# reflow.net
KiCad netlist of a schematic drawn in EAGLE
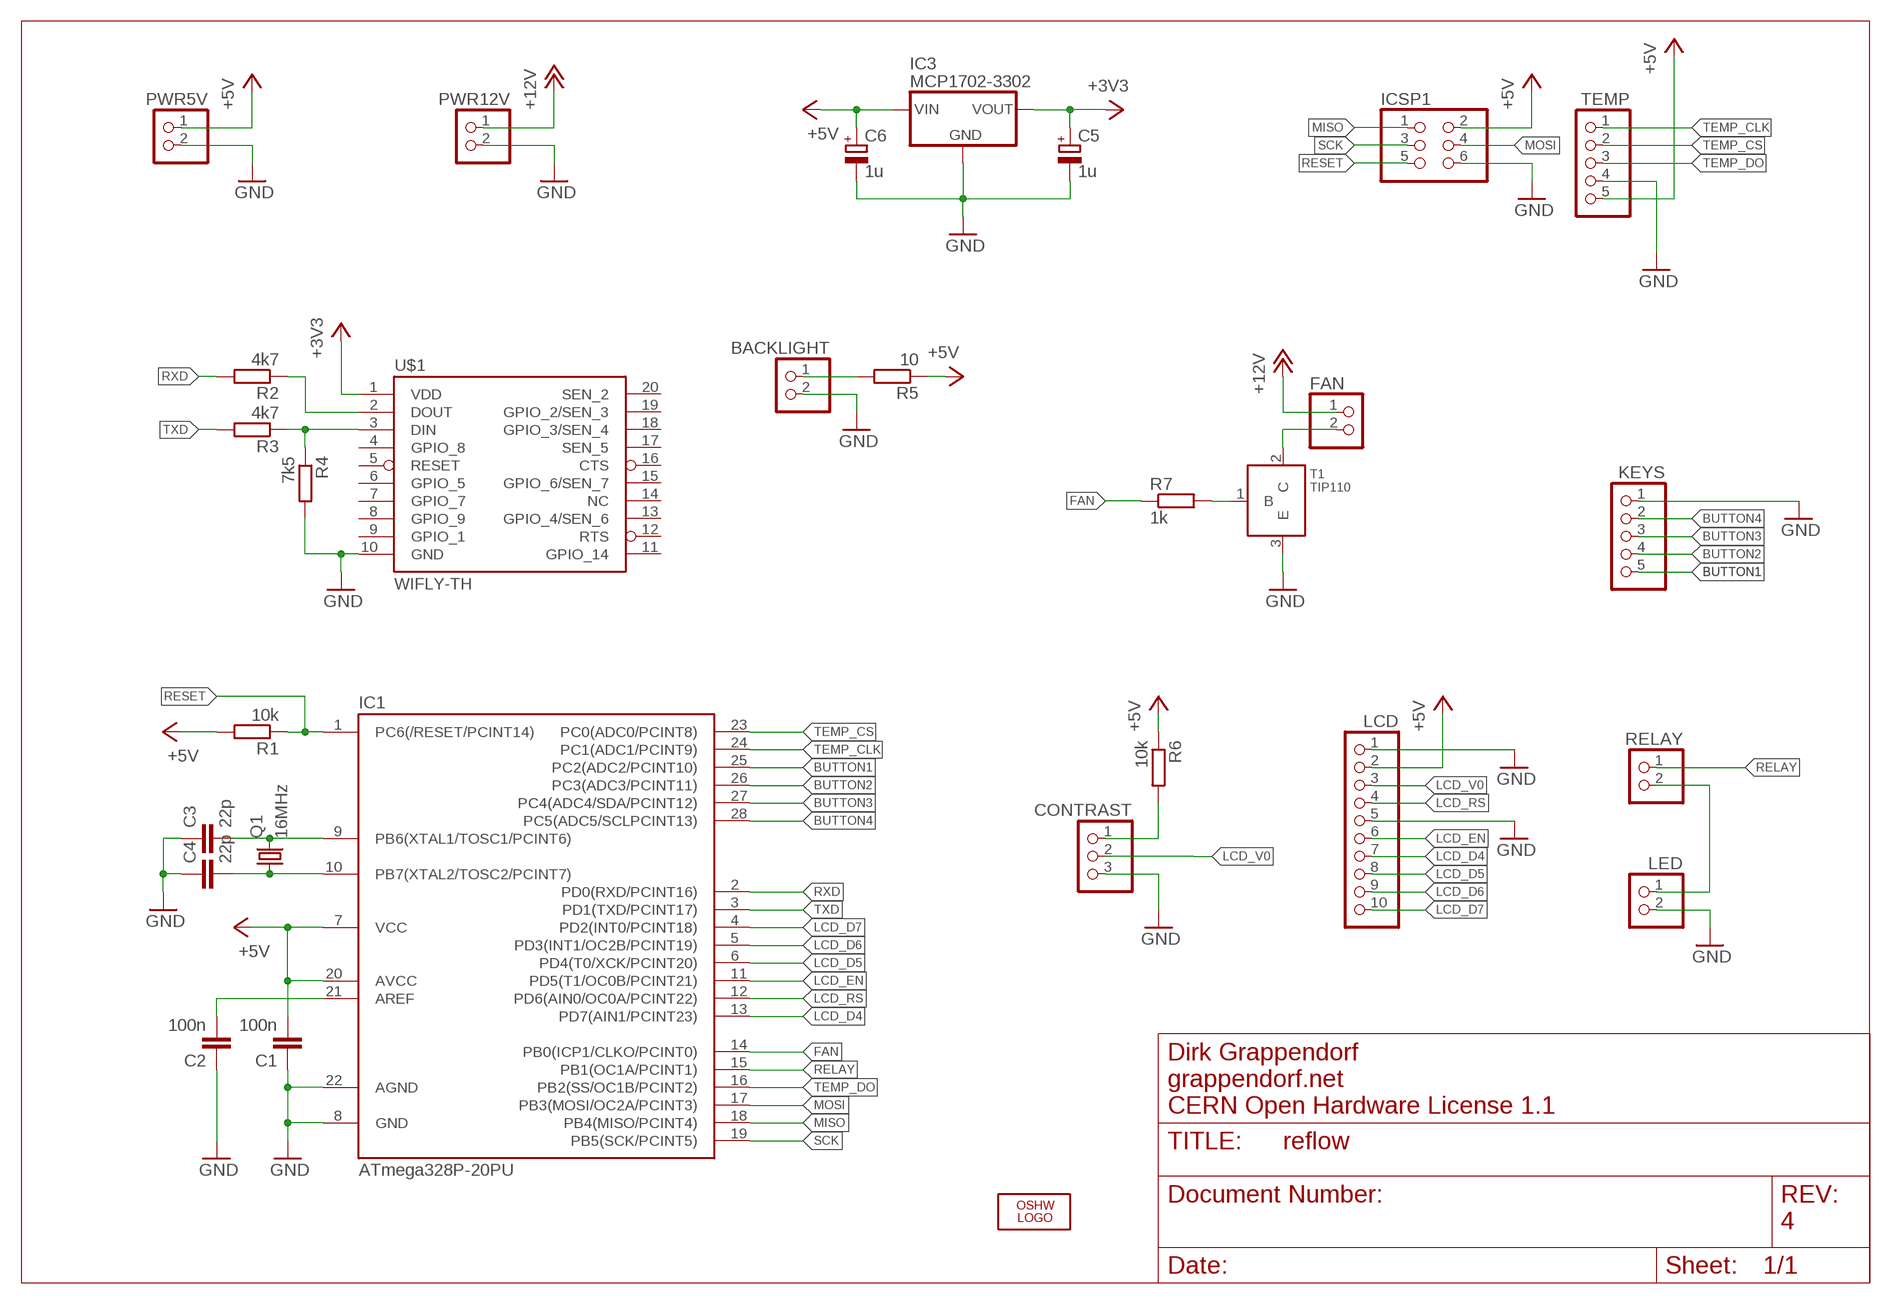
[diagram p0: schematic, sheet 1]

(export (version "E")
  (design (tool "Eeschema 10.0.6"))
  (components
    (comp (ref "BACKLIGHT")
      (value "PINHD-1X2")
      (footprint "eagle-import:1X02")
      (libsource (lib "eagle-import") (part "PINHD-1X2"))
    )
    (comp (ref "C1")
      (value "100n")
      (footprint "eagle-import:C025-024X044")
      (libsource (lib "eagle-import") (part "C-EU025-024X044"))
    )
    (comp (ref "C2")
      (value "100n")
      (footprint "eagle-import:C025-024X044")
      (libsource (lib "eagle-import") (part "C-EU025-024X044"))
    )
    (comp (ref "C3")
      (value "22p")
      (footprint "eagle-import:C025-025X050")
      (libsource (lib "eagle-import") (part "C-EU025-025X050"))
    )
    (comp (ref "C4")
      (value "22p")
      (footprint "eagle-import:C025-025X050")
      (libsource (lib "eagle-import") (part "C-EU025-025X050"))
    )
    (comp (ref "C5")
      (value "1u")
      (footprint "eagle-import:E2,5-5")
      (libsource (lib "eagle-import") (part "CPOL-EUE2.5-5"))
    )
    (comp (ref "C6")
      (value "1u")
      (footprint "eagle-import:E2,5-5")
      (libsource (lib "eagle-import") (part "CPOL-EUE2.5-5"))
    )
    (comp (ref "CONTRAST")
      (value "PINHD-1X3")
      (footprint "eagle-import:1X03")
      (libsource (lib "eagle-import") (part "PINHD-1X3"))
    )
    (comp (ref "FAN")
      (value "PINHD-1X2")
      (footprint "eagle-import:1X02")
      (libsource (lib "eagle-import") (part "PINHD-1X2"))
    )
    (comp (ref "IC1")
      (value "ATmega328P-20PU")
      (footprint "eagle-import:DIL28-3")
      (libsource (lib "eagle-import") (part "ATMEGA48/88/168-PU"))
    )
    (comp (ref "IC3")
      (value "MCP1702-3302")
      (footprint "eagle-import:MCP1702")
      (libsource (lib "eagle-import") (part "MCP1702"))
    )
    (comp (ref "ICSP1")
      (value "PINHD-2X03_2.54")
      (footprint "eagle-import:2X03")
      (libsource (lib "eagle-import") (part "PINHD-2X03_2.54"))
    )
    (comp (ref "KEYS")
      (value "PINHD-1X5")
      (footprint "eagle-import:1X05")
      (libsource (lib "eagle-import") (part "PINHD-1X5"))
    )
    (comp (ref "LCD")
      (value "PINHD-1X10")
      (footprint "eagle-import:1X10")
      (libsource (lib "eagle-import") (part "PINHD-1X10"))
    )
    (comp (ref "LED")
      (value "PINHD-1X2")
      (footprint "eagle-import:1X02")
      (libsource (lib "eagle-import") (part "PINHD-1X2"))
    )
    (comp (ref "LOGO1")
      (value "OSHW_LOGO_10MILX0350-NT-BOTTOM")
      (footprint "eagle-import:OSHW_10X350_NOTEXT_BOTTOM")
      (libsource (lib "eagle-import") (part "OSHW_LOGO_10MILX0350-NT-BOTTOM"))
    )
    (comp (ref "PWR5V")
      (value "PINHD-1X2")
      (footprint "eagle-import:1X02")
      (libsource (lib "eagle-import") (part "PINHD-1X2"))
    )
    (comp (ref "PWR12V")
      (value "PINHD-1X2")
      (footprint "eagle-import:1X02")
      (libsource (lib "eagle-import") (part "PINHD-1X2"))
    )
    (comp (ref "Q1")
      (value "16MHz")
      (footprint "eagle-import:HC49U-V")
      (libsource (lib "eagle-import") (part "CRYSTALHC49U-V"))
    )
    (comp (ref "R1")
      (value "10k")
      (footprint "eagle-import:0204_7")
      (libsource (lib "eagle-import") (part "R-EU_0204/7"))
    )
    (comp (ref "R2")
      (value "4k7")
      (footprint "eagle-import:0204_7")
      (libsource (lib "eagle-import") (part "R-EU_0204/7"))
    )
    (comp (ref "R3")
      (value "4k7")
      (footprint "eagle-import:0204_7")
      (libsource (lib "eagle-import") (part "R-EU_0204/7"))
    )
    (comp (ref "R4")
      (value "7k5")
      (footprint "eagle-import:0204_7")
      (libsource (lib "eagle-import") (part "R-EU_0204/7"))
    )
    (comp (ref "R5")
      (value "10")
      (footprint "eagle-import:0204_7")
      (libsource (lib "eagle-import") (part "R-EU_0204/7"))
    )
    (comp (ref "R6")
      (value "10k")
      (footprint "eagle-import:0204_7")
      (libsource (lib "eagle-import") (part "R-EU_0204/7"))
    )
    (comp (ref "R7")
      (value "1k")
      (footprint "eagle-import:0204_7")
      (libsource (lib "eagle-import") (part "R-EU_0204/7"))
    )
    (comp (ref "RELAY")
      (value "PINHD-1X2")
      (footprint "eagle-import:1X02")
      (libsource (lib "eagle-import") (part "PINHD-1X2"))
    )
    (comp (ref "T1")
      (value "TIP110")
      (footprint "eagle-import:T0220")
      (libsource (lib "eagle-import") (part "TIP112"))
    )
    (comp (ref "TEMP")
      (value "PINHD-1X5")
      (footprint "eagle-import:1X05")
      (libsource (lib "eagle-import") (part "PINHD-1X5"))
    )
    (comp (ref "U$1")
      (value "WIFLY-TH")
      (footprint "eagle-import:WIFLY-TH")
      (libsource (lib "eagle-import") (part "WIFLY-TH"))
    )
  )
  (nets
    (net (code "1") (name "+3V3") (class "Default")
      (node (ref "C5") (pin "+") (pinfunction "+_+") (pintype "passive"))
      (node (ref "IC3") (pin "VOUT") (pinfunction "OUT_VOUT") (pintype "passive"))
      (node (ref "U$1") (pin "1") (pinfunction "VDD_1") (pintype "power_in"))
    )
    (net (code "2") (name "+5V") (class "Default")
      (node (ref "C1") (pin "2") (pinfunction "2_2") (pintype "passive"))
      (node (ref "C6") (pin "+") (pinfunction "+_+") (pintype "passive"))
      (node (ref "IC1") (pin "20") (pinfunction "AVCC_20") (pintype "passive"))
      (node (ref "IC1") (pin "7") (pinfunction "VCC_7") (pintype "power_in"))
      (node (ref "IC3") (pin "VIN") (pinfunction "IN_VIN") (pintype "input"))
      (node (ref "ICSP1") (pin "2") (pinfunction "2_2") (pintype "passive"))
      (node (ref "LCD") (pin "2") (pinfunction "2_2") (pintype "passive"))
      (node (ref "PWR5V") (pin "1") (pinfunction "1_1") (pintype "passive"))
      (node (ref "R1") (pin "2") (pinfunction "2_2") (pintype "passive"))
      (node (ref "R5") (pin "1") (pinfunction "1_1") (pintype "passive"))
      (node (ref "R6") (pin "1") (pinfunction "1_1") (pintype "passive"))
      (node (ref "TEMP") (pin "5") (pinfunction "5_5") (pintype "passive"))
    )
    (net (code "3") (name "+12V") (class "Default")
      (node (ref "FAN") (pin "1") (pinfunction "1_1") (pintype "passive"))
      (node (ref "PWR12V") (pin "1") (pinfunction "1_1") (pintype "passive"))
    )
    (net (code "4") (name "BUTTON1") (class "Default")
      (node (ref "IC1") (pin "25") (pinfunction "PC2(ADC2/PCINT10)_25") (pintype "bidirectional"))
      (node (ref "KEYS") (pin "5") (pinfunction "5_5") (pintype "passive"))
    )
    (net (code "5") (name "BUTTON2") (class "Default")
      (node (ref "IC1") (pin "26") (pinfunction "PC3(ADC3/PCINT11)_26") (pintype "bidirectional"))
      (node (ref "KEYS") (pin "4") (pinfunction "4_4") (pintype "passive"))
    )
    (net (code "6") (name "BUTTON3") (class "Default")
      (node (ref "IC1") (pin "27") (pinfunction "PC4(ADC4/SDA/PCINT12)_27") (pintype "bidirectional"))
      (node (ref "KEYS") (pin "3") (pinfunction "3_3") (pintype "passive"))
    )
    (net (code "7") (name "BUTTON4") (class "Default")
      (node (ref "IC1") (pin "28") (pinfunction "PC5(ADC5/SCLPCINT13)_28") (pintype "bidirectional"))
      (node (ref "KEYS") (pin "2") (pinfunction "2_2") (pintype "passive"))
    )
    (net (code "8") (name "FAN") (class "Default")
      (node (ref "IC1") (pin "14") (pinfunction "PB0(ICP1/CLKO/PCINT0)_14") (pintype "bidirectional"))
      (node (ref "R7") (pin "1") (pinfunction "1_1") (pintype "passive"))
    )
    (net (code "9") (name "GND") (class "Default")
      (node (ref "BACKLIGHT") (pin "2") (pinfunction "2_2") (pintype "passive"))
      (node (ref "C1") (pin "1") (pinfunction "1_1") (pintype "passive"))
      (node (ref "C2") (pin "1") (pinfunction "1_1") (pintype "passive"))
      (node (ref "C3") (pin "1") (pinfunction "1_1") (pintype "passive"))
      (node (ref "C4") (pin "1") (pinfunction "1_1") (pintype "passive"))
      (node (ref "C5") (pin "-") (pinfunction "-_-") (pintype "passive"))
      (node (ref "C6") (pin "-") (pinfunction "-_-") (pintype "passive"))
      (node (ref "CONTRAST") (pin "3") (pinfunction "3_3") (pintype "passive"))
      (node (ref "IC1") (pin "22") (pinfunction "AGND_22") (pintype "power_in"))
      (node (ref "IC1") (pin "8") (pinfunction "GND_8") (pintype "power_in"))
      (node (ref "IC3") (pin "GND") (pinfunction "GND_GND") (pintype "input"))
      (node (ref "ICSP1") (pin "6") (pinfunction "6_6") (pintype "passive"))
      (node (ref "KEYS") (pin "1") (pinfunction "1_1") (pintype "passive"))
      (node (ref "LCD") (pin "1") (pinfunction "1_1") (pintype "passive"))
      (node (ref "LCD") (pin "5") (pinfunction "5_5") (pintype "passive"))
      (node (ref "LED") (pin "2") (pinfunction "2_2") (pintype "passive"))
      (node (ref "PWR12V") (pin "2") (pinfunction "2_2") (pintype "passive"))
      (node (ref "PWR5V") (pin "2") (pinfunction "2_2") (pintype "passive"))
      (node (ref "R4") (pin "2") (pinfunction "2_2") (pintype "passive"))
      (node (ref "T1") (pin "3") (pinfunction "E_3") (pintype "bidirectional"))
      (node (ref "TEMP") (pin "4") (pinfunction "4_4") (pintype "passive"))
      (node (ref "U$1") (pin "10") (pinfunction "GND_10") (pintype "power_in"))
    )
    (net (code "10") (name "LCD_D4") (class "Default")
      (node (ref "IC1") (pin "13") (pinfunction "PD7(AIN1/PCINT23)_13") (pintype "bidirectional"))
      (node (ref "LCD") (pin "7") (pinfunction "7_7") (pintype "passive"))
    )
    (net (code "11") (name "LCD_D5") (class "Default")
      (node (ref "IC1") (pin "6") (pinfunction "PD4(T0/XCK/PCINT20)_6") (pintype "bidirectional"))
      (node (ref "LCD") (pin "8") (pinfunction "8_8") (pintype "passive"))
    )
    (net (code "12") (name "LCD_D6") (class "Default")
      (node (ref "IC1") (pin "5") (pinfunction "PD3(INT1/OC2B/PCINT19)_5") (pintype "bidirectional"))
      (node (ref "LCD") (pin "9") (pinfunction "9_9") (pintype "passive"))
    )
    (net (code "13") (name "LCD_D7") (class "Default")
      (node (ref "IC1") (pin "4") (pinfunction "PD2(INT0/PCINT18)_4") (pintype "bidirectional"))
      (node (ref "LCD") (pin "10") (pinfunction "10_10") (pintype "passive"))
    )
    (net (code "14") (name "LCD_EN") (class "Default")
      (node (ref "IC1") (pin "11") (pinfunction "PD5(T1/OC0B/PCINT21)_11") (pintype "bidirectional"))
      (node (ref "LCD") (pin "6") (pinfunction "6_6") (pintype "passive"))
    )
    (net (code "15") (name "LCD_RS") (class "Default")
      (node (ref "IC1") (pin "12") (pinfunction "PD6(AIN0/OC0A/PCINT22)_12") (pintype "bidirectional"))
      (node (ref "LCD") (pin "4") (pinfunction "4_4") (pintype "passive"))
    )
    (net (code "16") (name "LCD_V0") (class "Default")
      (node (ref "CONTRAST") (pin "2") (pinfunction "2_2") (pintype "passive"))
      (node (ref "LCD") (pin "3") (pinfunction "3_3") (pintype "passive"))
    )
    (net (code "17") (name "MISO") (class "Default")
      (node (ref "IC1") (pin "18") (pinfunction "PB4(MISO/PCINT4)_18") (pintype "bidirectional"))
      (node (ref "ICSP1") (pin "1") (pinfunction "1_1") (pintype "passive"))
    )
    (net (code "18") (name "MOSI") (class "Default")
      (node (ref "IC1") (pin "17") (pinfunction "PB3(MOSI/OC2A/PCINT3)_17") (pintype "bidirectional"))
      (node (ref "ICSP1") (pin "4") (pinfunction "4_4") (pintype "passive"))
    )
    (net (code "19") (name "Net-(BACKLIGHT-Pad1)") (class "Default")
      (node (ref "BACKLIGHT") (pin "1") (pinfunction "1_1") (pintype "passive"))
      (node (ref "R5") (pin "2") (pinfunction "2_2") (pintype "passive"))
    )
    (net (code "20") (name "Net-(CONTRAST-Pad1)") (class "Default")
      (node (ref "CONTRAST") (pin "1") (pinfunction "1_1") (pintype "passive"))
      (node (ref "R6") (pin "2") (pinfunction "2_2") (pintype "passive"))
    )
    (net (code "21") (name "Net-(IC1-AREF)") (class "Default")
      (node (ref "C2") (pin "2") (pinfunction "2_2") (pintype "passive"))
      (node (ref "IC1") (pin "21") (pinfunction "AREF_21") (pintype "passive"))
    )
    (net (code "22") (name "Net-(IC1-PB6(XTAL1{slash}TOSC1{slash}PCINT6))") (class "Default")
      (node (ref "C3") (pin "2") (pinfunction "2_2") (pintype "passive"))
      (node (ref "IC1") (pin "9") (pinfunction "PB6(XTAL1/TOSC1/PCINT6)_9") (pintype "bidirectional"))
      (node (ref "Q1") (pin "2") (pinfunction "2_2") (pintype "passive"))
    )
    (net (code "23") (name "Net-(IC1-PB7(XTAL2{slash}TOSC2{slash}PCINT7))") (class "Default")
      (node (ref "C4") (pin "2") (pinfunction "2_2") (pintype "passive"))
      (node (ref "IC1") (pin "10") (pinfunction "PB7(XTAL2/TOSC2/PCINT7)_10") (pintype "bidirectional"))
      (node (ref "Q1") (pin "1") (pinfunction "1_1") (pintype "passive"))
    )
    (net (code "24") (name "Net-(LED-Pad1)") (class "Default")
      (node (ref "LED") (pin "1") (pinfunction "1_1") (pintype "passive"))
      (node (ref "RELAY") (pin "2") (pinfunction "2_2") (pintype "passive"))
    )
    (net (code "25") (name "Net-(T1-B)") (class "Default")
      (node (ref "R7") (pin "2") (pinfunction "2_2") (pintype "passive"))
      (node (ref "T1") (pin "1") (pinfunction "B_1") (pintype "bidirectional"))
    )
    (net (code "26") (name "Net-(T1-C)") (class "Default")
      (node (ref "FAN") (pin "2") (pinfunction "2_2") (pintype "passive"))
      (node (ref "T1") (pin "2") (pinfunction "C_2") (pintype "bidirectional"))
    )
    (net (code "27") (name "Net-(U$1-DIN)") (class "Default")
      (node (ref "R3") (pin "1") (pinfunction "1_1") (pintype "passive"))
      (node (ref "R4") (pin "1") (pinfunction "1_1") (pintype "passive"))
      (node (ref "U$1") (pin "3") (pinfunction "DIN_3") (pintype "input"))
    )
    (net (code "28") (name "Net-(U$1-DOUT)") (class "Default")
      (node (ref "R2") (pin "1") (pinfunction "1_1") (pintype "passive"))
      (node (ref "U$1") (pin "2") (pinfunction "DOUT_2") (pintype "output"))
    )
    (net (code "29") (name "RELAY") (class "Default")
      (node (ref "IC1") (pin "15") (pinfunction "PB1(OC1A/PCINT1)_15") (pintype "bidirectional"))
      (node (ref "RELAY") (pin "1") (pinfunction "1_1") (pintype "passive"))
    )
    (net (code "30") (name "RESET") (class "Default")
      (node (ref "IC1") (pin "1") (pinfunction "PC6(/RESET/PCINT14)_1") (pintype "bidirectional"))
      (node (ref "ICSP1") (pin "5") (pinfunction "5_5") (pintype "passive"))
      (node (ref "R1") (pin "1") (pinfunction "1_1") (pintype "passive"))
    )
    (net (code "31") (name "RXD") (class "Default")
      (node (ref "IC1") (pin "2") (pinfunction "PD0(RXD/PCINT16)_2") (pintype "bidirectional"))
      (node (ref "R2") (pin "2") (pinfunction "2_2") (pintype "passive"))
    )
    (net (code "32") (name "SCK") (class "Default")
      (node (ref "IC1") (pin "19") (pinfunction "PB5(SCK/PCINT5)_19") (pintype "bidirectional"))
      (node (ref "ICSP1") (pin "3") (pinfunction "3_3") (pintype "passive"))
    )
    (net (code "33") (name "TEMP_CLK") (class "Default")
      (node (ref "IC1") (pin "24") (pinfunction "PC1(ADC1/PCINT9)_24") (pintype "bidirectional"))
      (node (ref "TEMP") (pin "1") (pinfunction "1_1") (pintype "passive"))
    )
    (net (code "34") (name "TEMP_CS") (class "Default")
      (node (ref "IC1") (pin "23") (pinfunction "PC0(ADC0/PCINT8)_23") (pintype "bidirectional"))
      (node (ref "TEMP") (pin "2") (pinfunction "2_2") (pintype "passive"))
    )
    (net (code "35") (name "TEMP_DO") (class "Default")
      (node (ref "IC1") (pin "16") (pinfunction "PB2(SS/OC1B/PCINT2)_16") (pintype "bidirectional"))
      (node (ref "TEMP") (pin "3") (pinfunction "3_3") (pintype "passive"))
    )
    (net (code "36") (name "TXD") (class "Default")
      (node (ref "IC1") (pin "3") (pinfunction "PD1(TXD/PCINT17)_3") (pintype "bidirectional"))
      (node (ref "R3") (pin "2") (pinfunction "2_2") (pintype "passive"))
    )
    (net (code "37") (name "unconnected-(U$1-CTS-Pad16)") (class "Default")
      (node (ref "U$1") (pin "16") (pinfunction "CTS_16") (pintype "input"))
    )
    (net (code "38") (name "unconnected-(U$1-GPIO_1-Pad9)") (class "Default")
      (node (ref "U$1") (pin "9") (pinfunction "GPIO_1_9") (pintype "bidirectional"))
    )
    (net (code "39") (name "unconnected-(U$1-GPIO_2{slash}SEN_3-Pad19)") (class "Default")
      (node (ref "U$1") (pin "19") (pinfunction "GPIO_2/SEN_3_19") (pintype "bidirectional"))
    )
    (net (code "40") (name "unconnected-(U$1-GPIO_3{slash}SEN_4-Pad18)") (class "Default")
      (node (ref "U$1") (pin "18") (pinfunction "GPIO_3/SEN_4_18") (pintype "bidirectional"))
    )
    (net (code "41") (name "unconnected-(U$1-GPIO_4{slash}SEN_6-Pad13)") (class "Default")
      (node (ref "U$1") (pin "13") (pinfunction "GPIO_4/SEN_6_13") (pintype "bidirectional"))
    )
    (net (code "42") (name "unconnected-(U$1-GPIO_5-Pad6)") (class "Default")
      (node (ref "U$1") (pin "6") (pinfunction "GPIO_5_6") (pintype "bidirectional"))
    )
    (net (code "43") (name "unconnected-(U$1-GPIO_6{slash}SEN_7-Pad15)") (class "Default")
      (node (ref "U$1") (pin "15") (pinfunction "GPIO_6/SEN_7_15") (pintype "bidirectional"))
    )
    (net (code "44") (name "unconnected-(U$1-GPIO_7-Pad7)") (class "Default")
      (node (ref "U$1") (pin "7") (pinfunction "GPIO_7_7") (pintype "bidirectional"))
    )
    (net (code "45") (name "unconnected-(U$1-GPIO_8-Pad4)") (class "Default")
      (node (ref "U$1") (pin "4") (pinfunction "GPIO_8_4") (pintype "bidirectional"))
    )
    (net (code "46") (name "unconnected-(U$1-GPIO_9-Pad8)") (class "Default")
      (node (ref "U$1") (pin "8") (pinfunction "GPIO_9_8") (pintype "bidirectional"))
    )
    (net (code "47") (name "unconnected-(U$1-GPIO_14-Pad11)") (class "Default")
      (node (ref "U$1") (pin "11") (pinfunction "GPIO_14_11") (pintype "bidirectional"))
    )
    (net (code "48") (name "unconnected-(U$1-NC-Pad14)") (class "Default")
      (node (ref "U$1") (pin "14") (pinfunction "NC_14") (pintype "bidirectional"))
    )
    (net (code "49") (name "unconnected-(U$1-RESET-Pad5)") (class "Default")
      (node (ref "U$1") (pin "5") (pinfunction "RESET_5") (pintype "input"))
    )
    (net (code "50") (name "unconnected-(U$1-RTS-Pad12)") (class "Default")
      (node (ref "U$1") (pin "12") (pinfunction "RTS_12") (pintype "output"))
    )
    (net (code "51") (name "unconnected-(U$1-SEN_2-Pad20)") (class "Default")
      (node (ref "U$1") (pin "20") (pinfunction "SEN_2_20") (pintype "bidirectional"))
    )
    (net (code "52") (name "unconnected-(U$1-SEN_5-Pad17)") (class "Default")
      (node (ref "U$1") (pin "17") (pinfunction "SEN_5_17") (pintype "bidirectional"))
    )
  )
)
